# keyboard.net
KiCad netlist of a schematic drawn in EAGLE
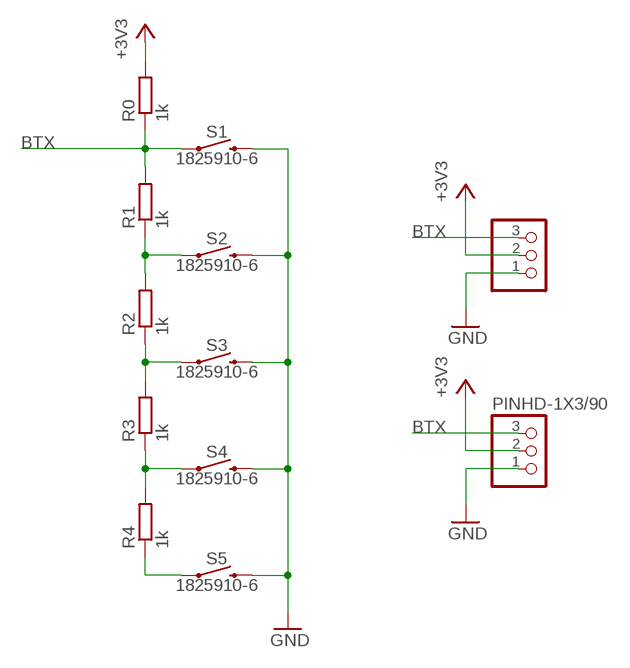
[diagram p0: schematic, sheet 1]

(export (version "E")
  (design (tool "Eeschema 10.0.6"))
  (components
    (comp (ref "JP1")
      (value "PINHD-1X3/90")
      (footprint "eagle-import:1X03_90")
      (fields (field (name "SPICEPREFIX") "J"))
      (libsource (lib "eagle-import") (part "PINHD-1X3/90"))
    )
    (comp (ref "JP2")
      (value "PINHD-1X3/90")
      (footprint "eagle-import:1X03_90")
      (libsource (lib "eagle-import") (part "PINHD-1X3/90"))
    )
    (comp (ref "R0")
      (value "1k")
      (footprint "eagle-import:R1206")
      (libsource (lib "eagle-import") (part "R-EU_R1206"))
    )
    (comp (ref "R1")
      (value "1k")
      (footprint "eagle-import:R1206")
      (libsource (lib "eagle-import") (part "R-EU_R1206"))
    )
    (comp (ref "R2")
      (value "1k")
      (footprint "eagle-import:R1206")
      (libsource (lib "eagle-import") (part "R-EU_R1206"))
    )
    (comp (ref "R3")
      (value "1k")
      (footprint "eagle-import:R1206")
      (libsource (lib "eagle-import") (part "R-EU_R1206"))
    )
    (comp (ref "R4")
      (value "1k")
      (footprint "eagle-import:R1206")
      (libsource (lib "eagle-import") (part "R-EU_R1206"))
    )
    (comp (ref "S1")
      (value "1825910-6")
      (footprint "eagle-import:1825910-6")
      (fields
        (field (name "DIGIKEY_PART_NUMBER") "450-1650-ND")
        (field (name "MANUFACTURER") "TE Connectivity ALCOSWITCH Switches")
        (field (name "CREATED_BY") " PCBLayout.com")
      )
      (libsource (lib "eagle-import") (part "1825910-6"))
    )
    (comp (ref "S2")
      (value "1825910-6")
      (footprint "eagle-import:1825910-6")
      (fields
        (field (name "DIGIKEY_PART_NUMBER") "450-1650-ND")
        (field (name "MANUFACTURER") "TE Connectivity ALCOSWITCH Switches")
        (field (name "CREATED_BY") " PCBLayout.com")
      )
      (libsource (lib "eagle-import") (part "1825910-6"))
    )
    (comp (ref "S3")
      (value "1825910-6")
      (footprint "eagle-import:1825910-6")
      (fields
        (field (name "DIGIKEY_PART_NUMBER") "450-1650-ND")
        (field (name "MANUFACTURER") "TE Connectivity ALCOSWITCH Switches")
        (field (name "CREATED_BY") " PCBLayout.com")
      )
      (libsource (lib "eagle-import") (part "1825910-6"))
    )
    (comp (ref "S4")
      (value "1825910-6")
      (footprint "eagle-import:1825910-6")
      (fields
        (field (name "DIGIKEY_PART_NUMBER") "450-1650-ND")
        (field (name "MANUFACTURER") "TE Connectivity ALCOSWITCH Switches")
        (field (name "CREATED_BY") " PCBLayout.com")
      )
      (libsource (lib "eagle-import") (part "1825910-6"))
    )
    (comp (ref "S5")
      (value "1825910-6")
      (footprint "eagle-import:1825910-6")
      (fields
        (field (name "DIGIKEY_PART_NUMBER") "450-1650-ND")
        (field (name "MANUFACTURER") "TE Connectivity ALCOSWITCH Switches")
        (field (name "CREATED_BY") " PCBLayout.com")
      )
      (libsource (lib "eagle-import") (part "1825910-6"))
    )
  )
  (nets
    (net (code "1") (name "+3V3") (class "Default")
      (node (ref "JP1") (pin "2") (pinfunction "2_2") (pintype "passive"))
      (node (ref "JP2") (pin "2") (pinfunction "2_2") (pintype "passive"))
      (node (ref "R0") (pin "2") (pinfunction "2_2") (pintype "passive"))
    )
    (net (code "2") (name "/BTX") (class "Default")
      (node (ref "JP1") (pin "3") (pinfunction "3_3") (pintype "passive"))
      (node (ref "JP2") (pin "3") (pinfunction "3_3") (pintype "passive"))
      (node (ref "R0") (pin "1") (pinfunction "1_1") (pintype "passive"))
      (node (ref "R1") (pin "2") (pinfunction "2_2") (pintype "passive"))
      (node (ref "S1") (pin "1") (pinfunction "1_1") (pintype "passive"))
      (node (ref "S1") (pin "3") (pinfunction "1_3") (pintype "passive"))
    )
    (net (code "3") (name "GND") (class "Default")
      (node (ref "JP1") (pin "1") (pinfunction "1_1") (pintype "passive"))
      (node (ref "JP2") (pin "1") (pinfunction "1_1") (pintype "passive"))
      (node (ref "S1") (pin "2") (pinfunction "2_2") (pintype "passive"))
      (node (ref "S1") (pin "4") (pinfunction "2_4") (pintype "passive"))
      (node (ref "S2") (pin "2") (pinfunction "2_2") (pintype "passive"))
      (node (ref "S2") (pin "4") (pinfunction "2_4") (pintype "passive"))
      (node (ref "S3") (pin "2") (pinfunction "2_2") (pintype "passive"))
      (node (ref "S3") (pin "4") (pinfunction "2_4") (pintype "passive"))
      (node (ref "S4") (pin "2") (pinfunction "2_2") (pintype "passive"))
      (node (ref "S4") (pin "4") (pinfunction "2_4") (pintype "passive"))
      (node (ref "S5") (pin "2") (pinfunction "2_2") (pintype "passive"))
      (node (ref "S5") (pin "4") (pinfunction "2_4") (pintype "passive"))
    )
    (net (code "4") (name "Net-(R1-Pad1)") (class "Default")
      (node (ref "R1") (pin "1") (pinfunction "1_1") (pintype "passive"))
      (node (ref "R2") (pin "2") (pinfunction "2_2") (pintype "passive"))
      (node (ref "S2") (pin "1") (pinfunction "1_1") (pintype "passive"))
      (node (ref "S2") (pin "3") (pinfunction "1_3") (pintype "passive"))
    )
    (net (code "5") (name "Net-(R2-Pad1)") (class "Default")
      (node (ref "R2") (pin "1") (pinfunction "1_1") (pintype "passive"))
      (node (ref "R3") (pin "2") (pinfunction "2_2") (pintype "passive"))
      (node (ref "S3") (pin "1") (pinfunction "1_1") (pintype "passive"))
      (node (ref "S3") (pin "3") (pinfunction "1_3") (pintype "passive"))
    )
    (net (code "6") (name "Net-(R3-Pad1)") (class "Default")
      (node (ref "R3") (pin "1") (pinfunction "1_1") (pintype "passive"))
      (node (ref "R4") (pin "2") (pinfunction "2_2") (pintype "passive"))
      (node (ref "S4") (pin "1") (pinfunction "1_1") (pintype "passive"))
      (node (ref "S4") (pin "3") (pinfunction "1_3") (pintype "passive"))
    )
    (net (code "7") (name "Net-(R4-Pad1)") (class "Default")
      (node (ref "R4") (pin "1") (pinfunction "1_1") (pintype "passive"))
      (node (ref "S5") (pin "1") (pinfunction "1_1") (pintype "passive"))
      (node (ref "S5") (pin "3") (pinfunction "1_3") (pintype "passive"))
    )
  )
)
